# pixelAdapter_l432_pro.net
KiCad netlist of a schematic drawn in EAGLE
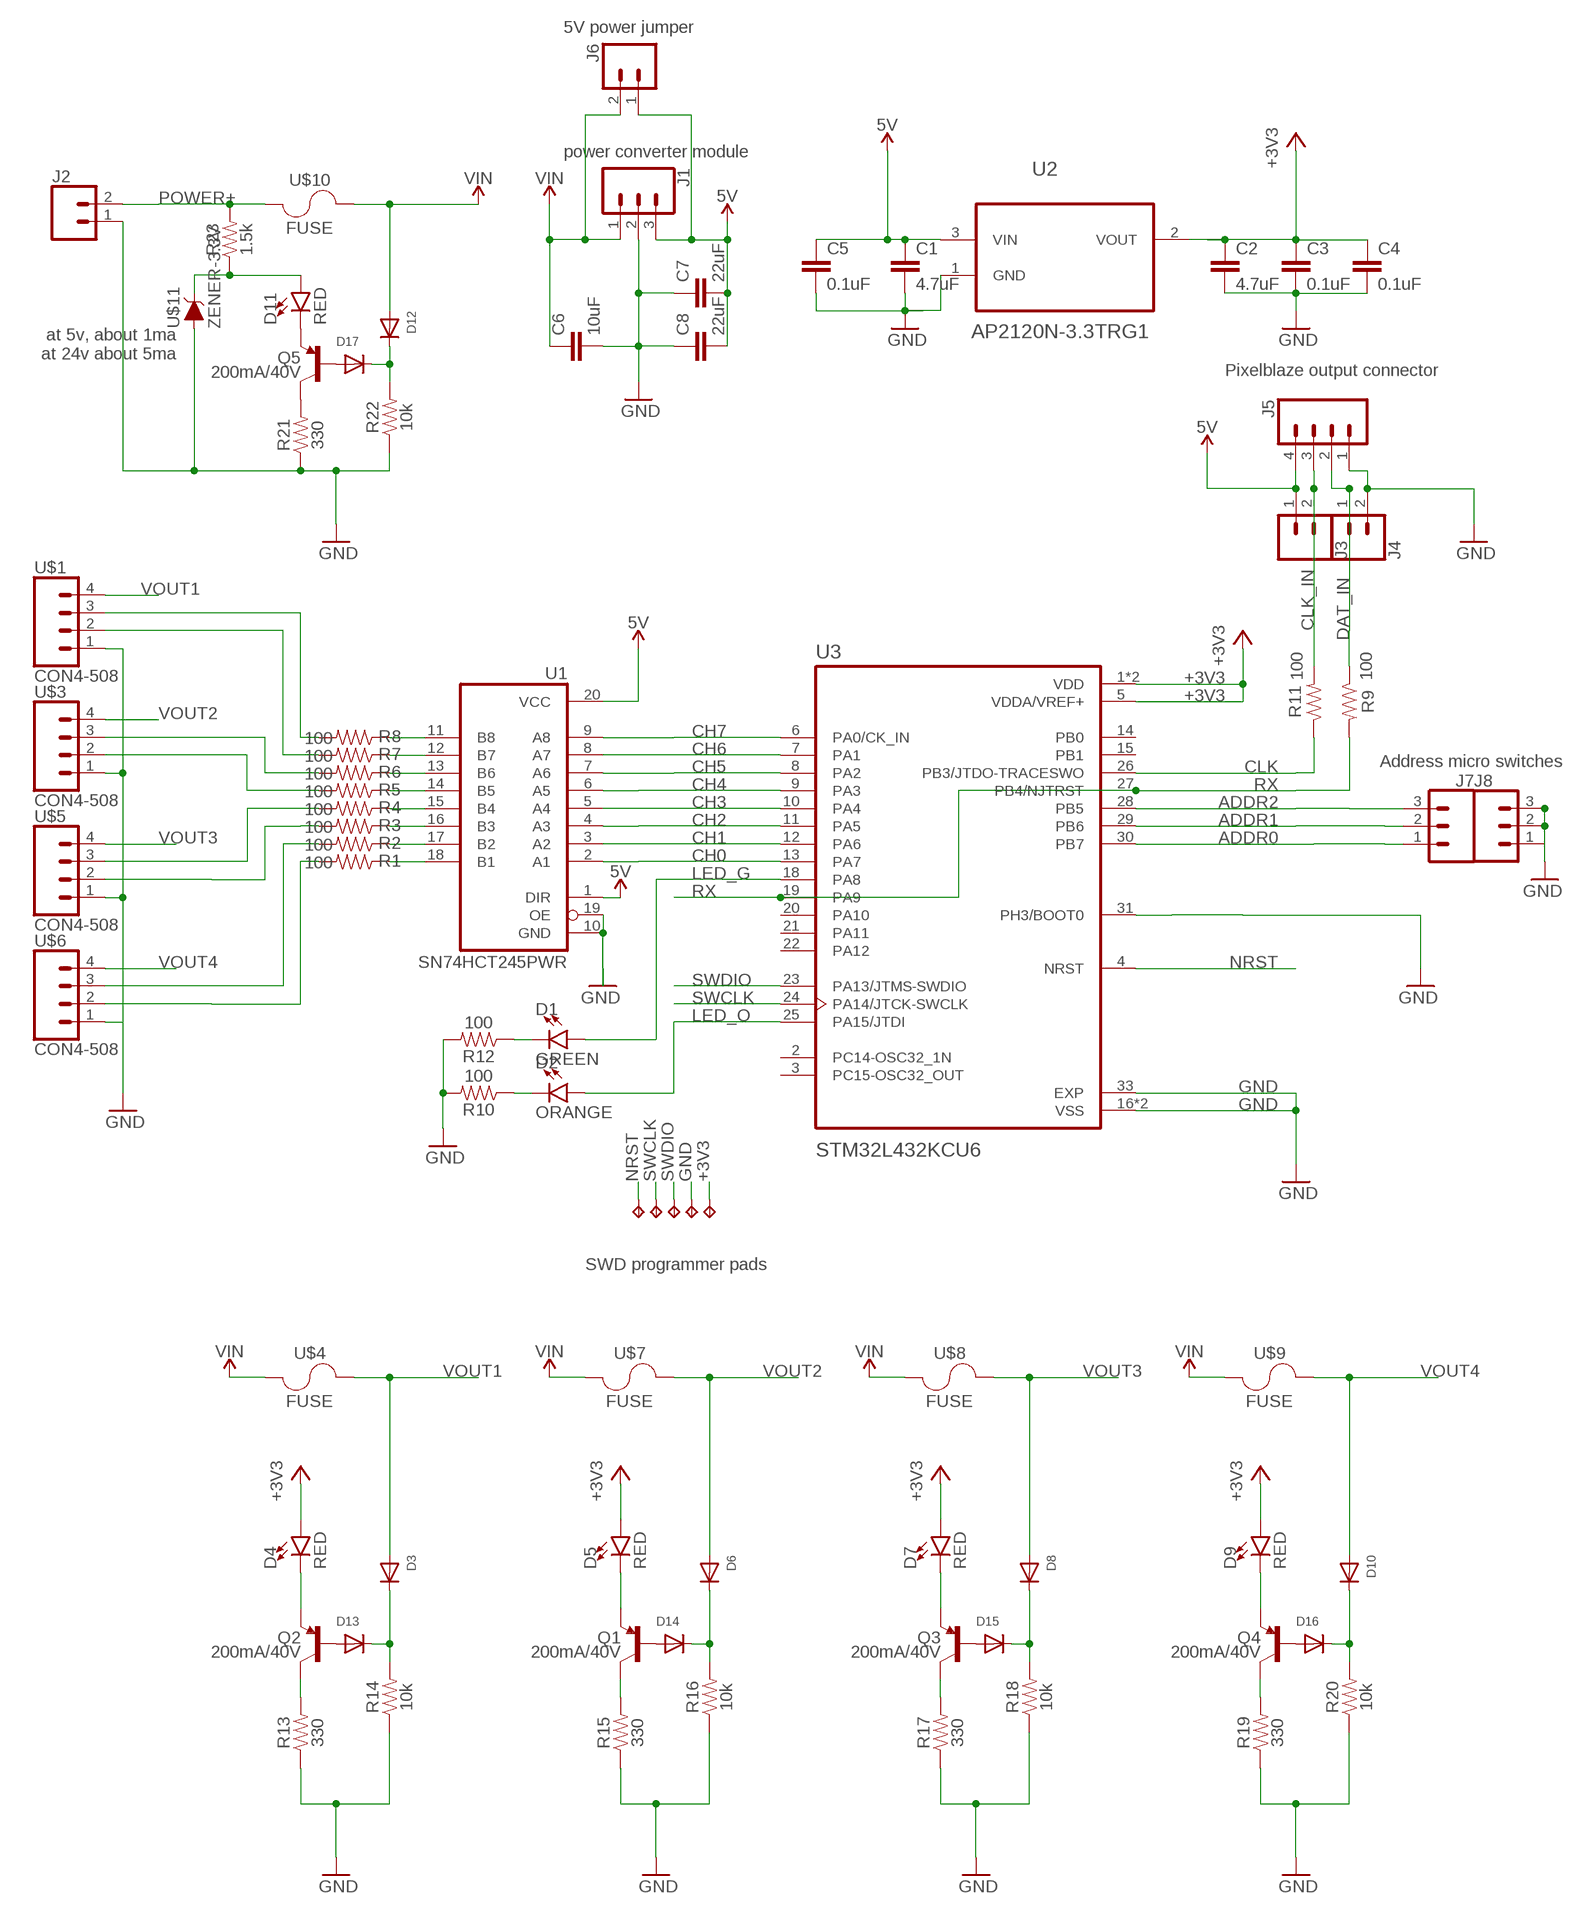
[diagram p0: schematic, sheet 1]

(export (version "E")
  (design (tool "Eeschema 10.0.6"))
  (components
    (comp (ref "C1")
      (value "4.7uF")
      (footprint "eagle-import:0603")
      (libsource (lib "eagle-import") (part "4.7UF0603"))
    )
    (comp (ref "C2")
      (value "4.7uF")
      (footprint "eagle-import:0603")
      (libsource (lib "eagle-import") (part "4.7UF0603"))
    )
    (comp (ref "C3")
      (value "0.1uF")
      (footprint "eagle-import:0603")
      (libsource (lib "eagle-import") (part "0.1UF-0603-25V-(+80/-20%)"))
    )
    (comp (ref "C4")
      (value "0.1uF")
      (footprint "eagle-import:0603")
      (libsource (lib "eagle-import") (part "0.1UF-0603-25V-(+80/-20%)"))
    )
    (comp (ref "C5")
      (value "0.1uF")
      (footprint "eagle-import:0603")
      (libsource (lib "eagle-import") (part "0.1UF-0603-25V-(+80/-20%)"))
    )
    (comp (ref "C6")
      (value "10uF")
      (footprint "eagle-import:1210")
      (libsource (lib "eagle-import") (part "10UF-1210-50V-20%"))
    )
    (comp (ref "C7")
      (value "22uF")
      (footprint "eagle-import:1210")
      (libsource (lib "eagle-import") (part "22UF-1210-16V-20%"))
    )
    (comp (ref "C8")
      (value "22uF")
      (footprint "eagle-import:1210")
      (libsource (lib "eagle-import") (part "22UF-1210-16V-20%"))
    )
    (comp (ref "D1")
      (value "GREEN")
      (footprint "eagle-import:LED-0603")
      (libsource (lib "eagle-import") (part "LED0603"))
    )
    (comp (ref "D2")
      (value "ORANGE")
      (footprint "eagle-import:LED-0603")
      (libsource (lib "eagle-import") (part "LED0603"))
    )
    (comp (ref "D3")
      (value "DIODESOD-123")
      (footprint "eagle-import:SOD-123")
      (libsource (lib "eagle-import") (part "DIODESOD-123"))
    )
    (comp (ref "D4")
      (value "RED")
      (footprint "eagle-import:LED-0603")
      (libsource (lib "eagle-import") (part "LED-RED0603"))
    )
    (comp (ref "D5")
      (value "RED")
      (footprint "eagle-import:LED-0603")
      (libsource (lib "eagle-import") (part "LED-RED0603"))
    )
    (comp (ref "D6")
      (value "DIODESOD-123")
      (footprint "eagle-import:SOD-123")
      (libsource (lib "eagle-import") (part "DIODESOD-123"))
    )
    (comp (ref "D7")
      (value "RED")
      (footprint "eagle-import:LED-0603")
      (libsource (lib "eagle-import") (part "LED-RED0603"))
    )
    (comp (ref "D8")
      (value "DIODESOD-123")
      (footprint "eagle-import:SOD-123")
      (libsource (lib "eagle-import") (part "DIODESOD-123"))
    )
    (comp (ref "D9")
      (value "RED")
      (footprint "eagle-import:LED-0603")
      (libsource (lib "eagle-import") (part "LED-RED0603"))
    )
    (comp (ref "D10")
      (value "DIODESOD-123")
      (footprint "eagle-import:SOD-123")
      (libsource (lib "eagle-import") (part "DIODESOD-123"))
    )
    (comp (ref "D11")
      (value "RED")
      (footprint "eagle-import:LED-0603")
      (libsource (lib "eagle-import") (part "LED-RED0603"))
    )
    (comp (ref "D12")
      (value "DIODESOD-123")
      (footprint "eagle-import:SOD-123")
      (libsource (lib "eagle-import") (part "DIODESOD-123"))
    )
    (comp (ref "D13")
      (value "DIODESOD-123")
      (footprint "eagle-import:SOD-123")
      (libsource (lib "eagle-import") (part "DIODESOD-123"))
    )
    (comp (ref "D14")
      (value "DIODESOD-123")
      (footprint "eagle-import:SOD-123")
      (libsource (lib "eagle-import") (part "DIODESOD-123"))
    )
    (comp (ref "D15")
      (value "DIODESOD-123")
      (footprint "eagle-import:SOD-123")
      (libsource (lib "eagle-import") (part "DIODESOD-123"))
    )
    (comp (ref "D16")
      (value "DIODESOD-123")
      (footprint "eagle-import:SOD-123")
      (libsource (lib "eagle-import") (part "DIODESOD-123"))
    )
    (comp (ref "D17")
      (value "DIODESOD-123")
      (footprint "eagle-import:SOD-123")
      (libsource (lib "eagle-import") (part "DIODESOD-123"))
    )
    (comp (ref "J1")
      (value "CONN_03")
      (footprint "eagle-import:1X03")
      (libsource (lib "eagle-import") (part "CONN_03"))
    )
    (comp (ref "J2")
      (value "CONN_025MM")
      (footprint "eagle-import:SCREWTERMINAL-5MM-2")
      (libsource (lib "eagle-import") (part "bens_CONN_025MM"))
    )
    (comp (ref "J3")
      (value "CONN_025MM")
      (footprint "eagle-import:SCREWTERMINAL-5MM-2")
      (libsource (lib "eagle-import") (part "bens_CONN_025MM"))
    )
    (comp (ref "J4")
      (value "CONN_025MM")
      (footprint "eagle-import:SCREWTERMINAL-5MM-2")
      (libsource (lib "eagle-import") (part "bens_CONN_025MM"))
    )
    (comp (ref "J5")
      (value "CONN_04LOCK")
      (footprint "eagle-import:1X04_LOCK")
      (libsource (lib "eagle-import") (part "CONN_04LOCK"))
    )
    (comp (ref "J6")
      (value "CONN_02")
      (footprint "eagle-import:1X02")
      (libsource (lib "eagle-import") (part "CONN_02"))
    )
    (comp (ref "J7")
      (value "CONN_03LOCK")
      (footprint "eagle-import:1X03_LOCK")
      (libsource (lib "eagle-import") (part "CONN_03LOCK"))
    )
    (comp (ref "J8")
      (value "CONN_03LOCK")
      (footprint "eagle-import:1X03_LOCK")
      (libsource (lib "eagle-import") (part "CONN_03LOCK"))
    )
    (comp (ref "Q1")
      (value "200mA/40V")
      (footprint "eagle-import:SOT23-3")
      (libsource (lib "eagle-import") (part "TRANS_PNP-PMBT3906|MMBT3906L"))
    )
    (comp (ref "Q2")
      (value "200mA/40V")
      (footprint "eagle-import:SOT23-3")
      (libsource (lib "eagle-import") (part "TRANS_PNP-PMBT3906|MMBT3906L"))
    )
    (comp (ref "Q3")
      (value "200mA/40V")
      (footprint "eagle-import:SOT23-3")
      (libsource (lib "eagle-import") (part "TRANS_PNP-PMBT3906|MMBT3906L"))
    )
    (comp (ref "Q4")
      (value "200mA/40V")
      (footprint "eagle-import:SOT23-3")
      (libsource (lib "eagle-import") (part "TRANS_PNP-PMBT3906|MMBT3906L"))
    )
    (comp (ref "Q5")
      (value "200mA/40V")
      (footprint "eagle-import:SOT23-3")
      (libsource (lib "eagle-import") (part "TRANS_PNP-PMBT3906|MMBT3906L"))
    )
    (comp (ref "R1")
      (value "100")
      (footprint "eagle-import:0603")
      (libsource (lib "eagle-import") (part "100OHM-0603-1/10W-1%"))
    )
    (comp (ref "R2")
      (value "100")
      (footprint "eagle-import:0603")
      (libsource (lib "eagle-import") (part "100OHM-0603-1/10W-1%"))
    )
    (comp (ref "R3")
      (value "100")
      (footprint "eagle-import:0603")
      (libsource (lib "eagle-import") (part "100OHM-0603-1/10W-1%"))
    )
    (comp (ref "R4")
      (value "100")
      (footprint "eagle-import:0603")
      (libsource (lib "eagle-import") (part "100OHM-0603-1/10W-1%"))
    )
    (comp (ref "R5")
      (value "100")
      (footprint "eagle-import:0603")
      (libsource (lib "eagle-import") (part "100OHM-0603-1/10W-1%"))
    )
    (comp (ref "R6")
      (value "100")
      (footprint "eagle-import:0603")
      (libsource (lib "eagle-import") (part "100OHM-0603-1/10W-1%"))
    )
    (comp (ref "R7")
      (value "100")
      (footprint "eagle-import:0603")
      (libsource (lib "eagle-import") (part "100OHM-0603-1/10W-1%"))
    )
    (comp (ref "R8")
      (value "100")
      (footprint "eagle-import:0603")
      (libsource (lib "eagle-import") (part "100OHM-0603-1/10W-1%"))
    )
    (comp (ref "R9")
      (value "100")
      (footprint "eagle-import:0603")
      (libsource (lib "eagle-import") (part "100OHM-0603-1/10W-1%"))
    )
    (comp (ref "R10")
      (value "100")
      (footprint "eagle-import:0603")
      (libsource (lib "eagle-import") (part "100OHM-0603-1/10W-1%"))
    )
    (comp (ref "R11")
      (value "100")
      (footprint "eagle-import:0603")
      (libsource (lib "eagle-import") (part "100OHM-0603-1/10W-1%"))
    )
    (comp (ref "R12")
      (value "100")
      (footprint "eagle-import:0603")
      (libsource (lib "eagle-import") (part "100OHM-0603-1/10W-1%"))
    )
    (comp (ref "R13")
      (value "330")
      (footprint "eagle-import:0603")
      (libsource (lib "eagle-import") (part "RESISTOR0603"))
    )
    (comp (ref "R14")
      (value "10k")
      (footprint "eagle-import:0603")
      (libsource (lib "eagle-import") (part "10KOHM-0603-1/10W-1%"))
    )
    (comp (ref "R15")
      (value "330")
      (footprint "eagle-import:0603")
      (libsource (lib "eagle-import") (part "RESISTOR0603"))
    )
    (comp (ref "R16")
      (value "10k")
      (footprint "eagle-import:0603")
      (libsource (lib "eagle-import") (part "10KOHM-0603-1/10W-1%"))
    )
    (comp (ref "R17")
      (value "330")
      (footprint "eagle-import:0603")
      (libsource (lib "eagle-import") (part "RESISTOR0603"))
    )
    (comp (ref "R18")
      (value "10k")
      (footprint "eagle-import:0603")
      (libsource (lib "eagle-import") (part "10KOHM-0603-1/10W-1%"))
    )
    (comp (ref "R19")
      (value "330")
      (footprint "eagle-import:0603")
      (libsource (lib "eagle-import") (part "RESISTOR0603"))
    )
    (comp (ref "R20")
      (value "10k")
      (footprint "eagle-import:0603")
      (libsource (lib "eagle-import") (part "10KOHM-0603-1/10W-1%"))
    )
    (comp (ref "R21")
      (value "330")
      (footprint "eagle-import:0603")
      (libsource (lib "eagle-import") (part "RESISTOR0603"))
    )
    (comp (ref "R22")
      (value "10k")
      (footprint "eagle-import:0603")
      (libsource (lib "eagle-import") (part "10KOHM-0603-1/10W-1%"))
    )
    (comp (ref "R23")
      (value "1.5k")
      (footprint "eagle-import:0603")
      (libsource (lib "eagle-import") (part "1.5KOHM-0603-1/10W-1%"))
    )
    (comp (ref "TP1")
      (value "TPTP20SQ")
      (footprint "eagle-import:TP20SQ")
      (libsource (lib "eagle-import") (part "TPTP20SQ"))
    )
    (comp (ref "TP2")
      (value "TPTP20SQ")
      (footprint "eagle-import:TP20SQ")
      (libsource (lib "eagle-import") (part "TPTP20SQ"))
    )
    (comp (ref "TP3")
      (value "TPTP20SQ")
      (footprint "eagle-import:TP20SQ")
      (libsource (lib "eagle-import") (part "TPTP20SQ"))
    )
    (comp (ref "TP4")
      (value "TPTP20SQ")
      (footprint "eagle-import:TP20SQ")
      (libsource (lib "eagle-import") (part "TPTP20SQ"))
    )
    (comp (ref "TP5")
      (value "TPTP20SQ")
      (footprint "eagle-import:TP20SQ")
      (libsource (lib "eagle-import") (part "TPTP20SQ"))
    )
    (comp (ref "U$1")
      (value "CON4-508")
      (footprint "eagle-import:CON4-508")
      (libsource (lib "eagle-import") (part "CON4-508"))
    )
    (comp (ref "U$3")
      (value "CON4-508")
      (footprint "eagle-import:CON4-508")
      (libsource (lib "eagle-import") (part "CON4-508"))
    )
    (comp (ref "U$4")
      (value "FUSE")
      (footprint "eagle-import:KEYSTONE-3586-FUSEHOLDER")
      (libsource (lib "eagle-import") (part "FUSE"))
    )
    (comp (ref "U$5")
      (value "CON4-508")
      (footprint "eagle-import:CON4-508")
      (libsource (lib "eagle-import") (part "CON4-508"))
    )
    (comp (ref "U$6")
      (value "CON4-508")
      (footprint "eagle-import:CON4-508")
      (libsource (lib "eagle-import") (part "CON4-508"))
    )
    (comp (ref "U$7")
      (value "FUSE")
      (footprint "eagle-import:KEYSTONE-3586-FUSEHOLDER")
      (libsource (lib "eagle-import") (part "FUSE"))
    )
    (comp (ref "U$8")
      (value "FUSE")
      (footprint "eagle-import:KEYSTONE-3586-FUSEHOLDER")
      (libsource (lib "eagle-import") (part "FUSE"))
    )
    (comp (ref "U$9")
      (value "FUSE")
      (footprint "eagle-import:KEYSTONE-3586-FUSEHOLDER")
      (libsource (lib "eagle-import") (part "FUSE"))
    )
    (comp (ref "U$10")
      (value "FUSE")
      (footprint "eagle-import:KEYSTONE-3586-FUSEHOLDER")
      (libsource (lib "eagle-import") (part "FUSE"))
    )
    (comp (ref "U$11")
      (value "ZENER-3.3V")
      (footprint "eagle-import:SOD-123FL")
      (libsource (lib "eagle-import") (part "ZENER"))
    )
    (comp (ref "U1")
      (value "SN74HCT245PWR")
      (footprint "eagle-import:TSSOP20")
      (libsource (lib "eagle-import") (part "74245PW"))
    )
    (comp (ref "U2")
      (value "AP2120N-3.3TRG1")
      (footprint "eagle-import:SOT95P237X112-3N")
      (fields (field (name "MPN") "MCP1700T-3302E/TT"))
      (libsource (lib "eagle-import") (part "MCP1700T-3302E/TT"))
    )
    (comp (ref "U3")
      (value "STM32L432KCU6")
      (footprint "eagle-import:QFN50P500X500X60-33N")
      (fields (field (name "MF") "STMicroelectronics"))
      (libsource (lib "eagle-import") (part "STM32L432KCU6"))
    )
  )
  (nets
    (net (code "1") (name "+3V3") (class "Default")
      (node (ref "C2") (pin "1") (pinfunction "1_1") (pintype "passive"))
      (node (ref "C3") (pin "1") (pinfunction "1_1") (pintype "passive"))
      (node (ref "C4") (pin "1") (pinfunction "1_1") (pintype "passive"))
      (node (ref "D4") (pin "A") (pinfunction "A_A") (pintype "passive"))
      (node (ref "D5") (pin "A") (pinfunction "A_A") (pintype "passive"))
      (node (ref "D7") (pin "A") (pinfunction "A_A") (pintype "passive"))
      (node (ref "D9") (pin "A") (pinfunction "A_A") (pintype "passive"))
      (node (ref "TP4") (pin "TP") (pinfunction "TP_TP") (pintype "input"))
      (node (ref "U2") (pin "2") (pinfunction "VOUT_2") (pintype "output"))
      (node (ref "U3") (pin "1") (pinfunction "VDD_1") (pintype "power_in"))
      (node (ref "U3") (pin "17") (pinfunction "VDD_17") (pintype "power_in"))
      (node (ref "U3") (pin "5") (pinfunction "VDDA/VREF+_5") (pintype "power_in"))
    )
    (net (code "2") (name "/ADDR0") (class "Default")
      (node (ref "J7") (pin "1") (pinfunction "1_1") (pintype "passive"))
      (node (ref "U3") (pin "30") (pinfunction "PB7_30") (pintype "bidirectional"))
    )
    (net (code "3") (name "/ADDR1") (class "Default")
      (node (ref "J7") (pin "2") (pinfunction "2_2") (pintype "passive"))
      (node (ref "U3") (pin "29") (pinfunction "PB6_29") (pintype "bidirectional"))
    )
    (net (code "4") (name "/ADDR2") (class "Default")
      (node (ref "J7") (pin "3") (pinfunction "3_3") (pintype "passive"))
      (node (ref "U3") (pin "28") (pinfunction "PB5_28") (pintype "bidirectional"))
    )
    (net (code "5") (name "/CH0") (class "Default")
      (node (ref "U1") (pin "2") (pinfunction "A1_2") (pintype "bidirectional"))
      (node (ref "U3") (pin "13") (pinfunction "PA7_13") (pintype "bidirectional"))
    )
    (net (code "6") (name "/CH1") (class "Default")
      (node (ref "U1") (pin "3") (pinfunction "A2_3") (pintype "bidirectional"))
      (node (ref "U3") (pin "12") (pinfunction "PA6_12") (pintype "bidirectional"))
    )
    (net (code "7") (name "/CH2") (class "Default")
      (node (ref "U1") (pin "4") (pinfunction "A3_4") (pintype "bidirectional"))
      (node (ref "U3") (pin "11") (pinfunction "PA5_11") (pintype "bidirectional"))
    )
    (net (code "8") (name "/CH3") (class "Default")
      (node (ref "U1") (pin "5") (pinfunction "A4_5") (pintype "bidirectional"))
      (node (ref "U3") (pin "10") (pinfunction "PA4_10") (pintype "bidirectional"))
    )
    (net (code "9") (name "/CH4") (class "Default")
      (node (ref "U1") (pin "6") (pinfunction "A5_6") (pintype "bidirectional"))
      (node (ref "U3") (pin "9") (pinfunction "PA3_9") (pintype "bidirectional"))
    )
    (net (code "10") (name "/CH5") (class "Default")
      (node (ref "U1") (pin "7") (pinfunction "A6_7") (pintype "bidirectional"))
      (node (ref "U3") (pin "8") (pinfunction "PA2_8") (pintype "bidirectional"))
    )
    (net (code "11") (name "/CH6") (class "Default")
      (node (ref "U1") (pin "8") (pinfunction "A7_8") (pintype "bidirectional"))
      (node (ref "U3") (pin "7") (pinfunction "PA1_7") (pintype "bidirectional"))
    )
    (net (code "12") (name "/CH7") (class "Default")
      (node (ref "U1") (pin "9") (pinfunction "A8_9") (pintype "bidirectional"))
      (node (ref "U3") (pin "6") (pinfunction "PA0/CK_IN_6") (pintype "bidirectional"))
    )
    (net (code "13") (name "/CLK") (class "Default")
      (node (ref "R11") (pin "1") (pinfunction "1_1") (pintype "passive"))
      (node (ref "U3") (pin "26") (pinfunction "PB3/JTDO-TRACESWO_26") (pintype "bidirectional"))
    )
    (net (code "14") (name "/CLK_IN") (class "Default")
      (node (ref "J3") (pin "2") (pinfunction "2_2") (pintype "passive"))
      (node (ref "J5") (pin "3") (pinfunction "3_3") (pintype "passive"))
      (node (ref "R11") (pin "2") (pinfunction "2_2") (pintype "passive"))
    )
    (net (code "15") (name "/DAT_IN") (class "Default")
      (node (ref "J4") (pin "1") (pinfunction "1_1") (pintype "passive"))
      (node (ref "J5") (pin "2") (pinfunction "2_2") (pintype "passive"))
      (node (ref "R9") (pin "1") (pinfunction "1_1") (pintype "passive"))
    )
    (net (code "16") (name "/LED_G") (class "Default")
      (node (ref "D1") (pin "A") (pinfunction "A_A") (pintype "passive"))
      (node (ref "U3") (pin "18") (pinfunction "PA8_18") (pintype "bidirectional"))
    )
    (net (code "17") (name "/LED_O") (class "Default")
      (node (ref "D2") (pin "A") (pinfunction "A_A") (pintype "passive"))
      (node (ref "U3") (pin "25") (pinfunction "PA15/JTDI_25") (pintype "bidirectional"))
    )
    (net (code "18") (name "/NRST") (class "Default")
      (node (ref "TP5") (pin "TP") (pinfunction "TP_TP") (pintype "input"))
      (node (ref "U3") (pin "4") (pinfunction "NRST_4") (pintype "bidirectional"))
    )
    (net (code "19") (name "/POWER+") (class "Default")
      (node (ref "J2") (pin "2") (pinfunction "2_2") (pintype "passive"))
      (node (ref "R23") (pin "2") (pinfunction "2_2") (pintype "passive"))
      (node (ref "U$10") (pin "A1") (pinfunction "1_A1") (pintype "bidirectional"))
      (node (ref "U$10") (pin "A2") (pinfunction "1_A2") (pintype "bidirectional"))
      (node (ref "U$10") (pin "A3") (pinfunction "1_A3") (pintype "bidirectional"))
    )
    (net (code "20") (name "/RX") (class "Default")
      (node (ref "R9") (pin "2") (pinfunction "2_2") (pintype "passive"))
      (node (ref "U3") (pin "19") (pinfunction "PA9_19") (pintype "bidirectional"))
      (node (ref "U3") (pin "27") (pinfunction "PB4/NJTRST_27") (pintype "bidirectional"))
    )
    (net (code "21") (name "/SWCLK") (class "Default")
      (node (ref "TP1") (pin "TP") (pinfunction "TP_TP") (pintype "input"))
      (node (ref "U3") (pin "24") (pinfunction "PA14/JTCK-SWCLK_24") (pintype "bidirectional"))
    )
    (net (code "22") (name "/SWDIO") (class "Default")
      (node (ref "TP2") (pin "TP") (pinfunction "TP_TP") (pintype "input"))
      (node (ref "U3") (pin "23") (pinfunction "PA13/JTMS-SWDIO_23") (pintype "bidirectional"))
    )
    (net (code "23") (name "/VOUT1") (class "Default")
      (node (ref "D3") (pin "A") (pinfunction "A_A") (pintype "passive"))
      (node (ref "U$1") (pin "4") (pinfunction "4_4") (pintype "passive"))
      (node (ref "U$4") (pin "B1") (pinfunction "2_B1") (pintype "bidirectional"))
      (node (ref "U$4") (pin "B2") (pinfunction "2_B2") (pintype "bidirectional"))
      (node (ref "U$4") (pin "B3") (pinfunction "2_B3") (pintype "bidirectional"))
    )
    (net (code "24") (name "/VOUT2") (class "Default")
      (node (ref "D6") (pin "A") (pinfunction "A_A") (pintype "passive"))
      (node (ref "U$3") (pin "4") (pinfunction "4_4") (pintype "passive"))
      (node (ref "U$7") (pin "B1") (pinfunction "2_B1") (pintype "bidirectional"))
      (node (ref "U$7") (pin "B2") (pinfunction "2_B2") (pintype "bidirectional"))
      (node (ref "U$7") (pin "B3") (pinfunction "2_B3") (pintype "bidirectional"))
    )
    (net (code "25") (name "/VOUT3") (class "Default")
      (node (ref "D8") (pin "A") (pinfunction "A_A") (pintype "passive"))
      (node (ref "U$5") (pin "4") (pinfunction "4_4") (pintype "passive"))
      (node (ref "U$8") (pin "B1") (pinfunction "2_B1") (pintype "bidirectional"))
      (node (ref "U$8") (pin "B2") (pinfunction "2_B2") (pintype "bidirectional"))
      (node (ref "U$8") (pin "B3") (pinfunction "2_B3") (pintype "bidirectional"))
    )
    (net (code "26") (name "/VOUT4") (class "Default")
      (node (ref "D10") (pin "A") (pinfunction "A_A") (pintype "passive"))
      (node (ref "U$6") (pin "4") (pinfunction "4_4") (pintype "passive"))
      (node (ref "U$9") (pin "B1") (pinfunction "2_B1") (pintype "bidirectional"))
      (node (ref "U$9") (pin "B2") (pinfunction "2_B2") (pintype "bidirectional"))
      (node (ref "U$9") (pin "B3") (pinfunction "2_B3") (pintype "bidirectional"))
    )
    (net (code "27") (name "5V") (class "Default")
      (node (ref "C1") (pin "1") (pinfunction "1_1") (pintype "passive"))
      (node (ref "C5") (pin "1") (pinfunction "1_1") (pintype "passive"))
      (node (ref "C7") (pin "2") (pinfunction "2_2") (pintype "passive"))
      (node (ref "C8") (pin "2") (pinfunction "2_2") (pintype "passive"))
      (node (ref "J1") (pin "3") (pinfunction "3_3") (pintype "passive"))
      (node (ref "J3") (pin "1") (pinfunction "1_1") (pintype "passive"))
      (node (ref "J5") (pin "4") (pinfunction "4_4") (pintype "passive"))
      (node (ref "J6") (pin "1") (pinfunction "1_1") (pintype "passive"))
      (node (ref "U1") (pin "1") (pinfunction "DIR_1") (pintype "input"))
      (node (ref "U1") (pin "20") (pinfunction "VCC_20") (pintype "bidirectional"))
      (node (ref "U2") (pin "3") (pinfunction "VIN_3") (pintype "input"))
    )
    (net (code "28") (name "GND") (class "Default")
      (node (ref "C1") (pin "2") (pinfunction "2_2") (pintype "passive"))
      (node (ref "C2") (pin "2") (pinfunction "2_2") (pintype "passive"))
      (node (ref "C3") (pin "2") (pinfunction "2_2") (pintype "passive"))
      (node (ref "C4") (pin "2") (pinfunction "2_2") (pintype "passive"))
      (node (ref "C5") (pin "2") (pinfunction "2_2") (pintype "passive"))
      (node (ref "C6") (pin "2") (pinfunction "2_2") (pintype "passive"))
      (node (ref "C7") (pin "1") (pinfunction "1_1") (pintype "passive"))
      (node (ref "C8") (pin "1") (pinfunction "1_1") (pintype "passive"))
      (node (ref "J1") (pin "2") (pinfunction "2_2") (pintype "passive"))
      (node (ref "J2") (pin "1") (pinfunction "1_1") (pintype "passive"))
      (node (ref "J4") (pin "2") (pinfunction "2_2") (pintype "passive"))
      (node (ref "J5") (pin "1") (pinfunction "1_1") (pintype "passive"))
      (node (ref "J8") (pin "1") (pinfunction "1_1") (pintype "passive"))
      (node (ref "J8") (pin "2") (pinfunction "2_2") (pintype "passive"))
      (node (ref "J8") (pin "3") (pinfunction "3_3") (pintype "passive"))
      (node (ref "R10") (pin "2") (pinfunction "2_2") (pintype "passive"))
      (node (ref "R12") (pin "2") (pinfunction "2_2") (pintype "passive"))
      (node (ref "R13") (pin "1") (pinfunction "1_1") (pintype "passive"))
      (node (ref "R14") (pin "1") (pinfunction "1_1") (pintype "passive"))
      (node (ref "R15") (pin "1") (pinfunction "1_1") (pintype "passive"))
      (node (ref "R16") (pin "1") (pinfunction "1_1") (pintype "passive"))
      (node (ref "R17") (pin "1") (pinfunction "1_1") (pintype "passive"))
      (node (ref "R18") (pin "1") (pinfunction "1_1") (pintype "passive"))
      (node (ref "R19") (pin "1") (pinfunction "1_1") (pintype "passive"))
      (node (ref "R20") (pin "1") (pinfunction "1_1") (pintype "passive"))
      (node (ref "R21") (pin "1") (pinfunction "1_1") (pintype "passive"))
      (node (ref "R22") (pin "1") (pinfunction "1_1") (pintype "passive"))
      (node (ref "TP3") (pin "TP") (pinfunction "TP_TP") (pintype "input"))
      (node (ref "U$1") (pin "1") (pinfunction "1_1") (pintype "passive"))
      (node (ref "U$11") (pin "A") (pinfunction "A_A") (pintype "passive"))
      (node (ref "U$3") (pin "1") (pinfunction "1_1") (pintype "passive"))
      (node (ref "U$5") (pin "1") (pinfunction "1_1") (pintype "passive"))
      (node (ref "U$6") (pin "1") (pinfunction "1_1") (pintype "passive"))
      (node (ref "U1") (pin "10") (pinfunction "GND_10") (pintype "bidirectional"))
      (node (ref "U1") (pin "19") (pinfunction "OE_19") (pintype "input"))
      (node (ref "U2") (pin "1") (pinfunction "GND_1") (pintype "passive"))
      (node (ref "U3") (pin "16") (pinfunction "VSS_16") (pintype "power_in"))
      (node (ref "U3") (pin "31") (pinfunction "PH3/BOOT0_31") (pintype "bidirectional"))
      (node (ref "U3") (pin "32") (pinfunction "VSS_32") (pintype "power_in"))
      (node (ref "U3") (pin "33") (pinfunction "EXP_33") (pintype "power_in"))
    )
    (net (code "29") (name "Net-(D1-PadC)") (class "Default")
      (node (ref "D1") (pin "C") (pinfunction "C_C") (pintype "passive"))
      (node (ref "R12") (pin "1") (pinfunction "1_1") (pintype "passive"))
    )
    (net (code "30") (name "Net-(D2-PadC)") (class "Default")
      (node (ref "D2") (pin "C") (pinfunction "C_C") (pintype "passive"))
      (node (ref "R10") (pin "1") (pinfunction "1_1") (pintype "passive"))
    )
    (net (code "31") (name "Net-(D10-PadC)") (class "Default")
      (node (ref "D10") (pin "C") (pinfunction "C_C") (pintype "passive"))
      (node (ref "D16") (pin "C") (pinfunction "C_C") (pintype "passive"))
      (node (ref "R20") (pin "2") (pinfunction "2_2") (pintype "passive"))
    )
    (net (code "32") (name "Net-(D11-PadA)") (class "Default")
      (node (ref "D11") (pin "A") (pinfunction "A_A") (pintype "passive"))
      (node (ref "R23") (pin "1") (pinfunction "1_1") (pintype "passive"))
      (node (ref "U$11") (pin "C") (pinfunction "C_C") (pintype "passive"))
    )
    (net (code "33") (name "Net-(D12-PadC)") (class "Default")
      (node (ref "D12") (pin "C") (pinfunction "C_C") (pintype "passive"))
      (node (ref "D17") (pin "C") (pinfunction "C_C") (pintype "passive"))
      (node (ref "R22") (pin "2") (pinfunction "2_2") (pintype "passive"))
    )
    (net (code "34") (name "Net-(D13-PadC)") (class "Default")
      (node (ref "D13") (pin "C") (pinfunction "C_C") (pintype "passive"))
      (node (ref "D3") (pin "C") (pinfunction "C_C") (pintype "passive"))
      (node (ref "R14") (pin "2") (pinfunction "2_2") (pintype "passive"))
    )
    (net (code "35") (name "Net-(D14-PadC)") (class "Default")
      (node (ref "D14") (pin "C") (pinfunction "C_C") (pintype "passive"))
      (node (ref "D6") (pin "C") (pinfunction "C_C") (pintype "passive"))
      (node (ref "R16") (pin "2") (pinfunction "2_2") (pintype "passive"))
    )
    (net (code "36") (name "Net-(D15-PadC)") (class "Default")
      (node (ref "D15") (pin "C") (pinfunction "C_C") (pintype "passive"))
      (node (ref "D8") (pin "C") (pinfunction "C_C") (pintype "passive"))
      (node (ref "R18") (pin "2") (pinfunction "2_2") (pintype "passive"))
    )
    (net (code "37") (name "Net-(Q1-B)") (class "Default")
      (node (ref "D14") (pin "A") (pinfunction "A_A") (pintype "passive"))
      (node (ref "Q1") (pin "1") (pinfunction "B_1") (pintype "passive"))
    )
    (net (code "38") (name "Net-(Q1-C)") (class "Default")
      (node (ref "Q1") (pin "3") (pinfunction "C_3") (pintype "passive"))
      (node (ref "R15") (pin "2") (pinfunction "2_2") (pintype "passive"))
    )
    (net (code "39") (name "Net-(Q1-E)") (class "Default")
      (node (ref "D5") (pin "C") (pinfunction "C_C") (pintype "passive"))
      (node (ref "Q1") (pin "2") (pinfunction "E_2") (pintype "passive"))
    )
    (net (code "40") (name "Net-(Q2-B)") (class "Default")
      (node (ref "D13") (pin "A") (pinfunction "A_A") (pintype "passive"))
      (node (ref "Q2") (pin "1") (pinfunction "B_1") (pintype "passive"))
    )
    (net (code "41") (name "Net-(Q2-C)") (class "Default")
      (node (ref "Q2") (pin "3") (pinfunction "C_3") (pintype "passive"))
      (node (ref "R13") (pin "2") (pinfunction "2_2") (pintype "passive"))
    )
    (net (code "42") (name "Net-(Q2-E)") (class "Default")
      (node (ref "D4") (pin "C") (pinfunction "C_C") (pintype "passive"))
      (node (ref "Q2") (pin "2") (pinfunction "E_2") (pintype "passive"))
    )
    (net (code "43") (name "Net-(Q3-B)") (class "Default")
      (node (ref "D15") (pin "A") (pinfunction "A_A") (pintype "passive"))
      (node (ref "Q3") (pin "1") (pinfunction "B_1") (pintype "passive"))
    )
    (net (code "44") (name "Net-(Q3-C)") (class "Default")
      (node (ref "Q3") (pin "3") (pinfunction "C_3") (pintype "passive"))
      (node (ref "R17") (pin "2") (pinfunction "2_2") (pintype "passive"))
    )
    (net (code "45") (name "Net-(Q3-E)") (class "Default")
      (node (ref "D7") (pin "C") (pinfunction "C_C") (pintype "passive"))
      (node (ref "Q3") (pin "2") (pinfunction "E_2") (pintype "passive"))
    )
    (net (code "46") (name "Net-(Q4-B)") (class "Default")
      (node (ref "D16") (pin "A") (pinfunction "A_A") (pintype "passive"))
      (node (ref "Q4") (pin "1") (pinfunction "B_1") (pintype "passive"))
    )
    (net (code "47") (name "Net-(Q4-C)") (class "Default")
      (node (ref "Q4") (pin "3") (pinfunction "C_3") (pintype "passive"))
      (node (ref "R19") (pin "2") (pinfunction "2_2") (pintype "passive"))
    )
    (net (code "48") (name "Net-(Q4-E)") (class "Default")
      (node (ref "D9") (pin "C") (pinfunction "C_C") (pintype "passive"))
      (node (ref "Q4") (pin "2") (pinfunction "E_2") (pintype "passive"))
    )
    (net (code "49") (name "Net-(Q5-B)") (class "Default")
      (node (ref "D17") (pin "A") (pinfunction "A_A") (pintype "passive"))
      (node (ref "Q5") (pin "1") (pinfunction "B_1") (pintype "passive"))
    )
    (net (code "50") (name "Net-(Q5-C)") (class "Default")
      (node (ref "Q5") (pin "3") (pinfunction "C_3") (pintype "passive"))
      (node (ref "R21") (pin "2") (pinfunction "2_2") (pintype "passive"))
    )
    (net (code "51") (name "Net-(Q5-E)") (class "Default")
      (node (ref "D11") (pin "C") (pinfunction "C_C") (pintype "passive"))
      (node (ref "Q5") (pin "2") (pinfunction "E_2") (pintype "passive"))
    )
    (net (code "52") (name "Net-(R1-Pad2)") (class "Default")
      (node (ref "R1") (pin "2") (pinfunction "2_2") (pintype "passive"))
      (node (ref "U$6") (pin "2") (pinfunction "2_2") (pintype "passive"))
    )
    (net (code "53") (name "Net-(R2-Pad2)") (class "Default")
      (node (ref "R2") (pin "2") (pinfunction "2_2") (pintype "passive"))
      (node (ref "U$6") (pin "3") (pinfunction "3_3") (pintype "passive"))
    )
    (net (code "54") (name "Net-(R3-Pad2)") (class "Default")
      (node (ref "R3") (pin "2") (pinfunction "2_2") (pintype "passive"))
      (node (ref "U$5") (pin "2") (pinfunction "2_2") (pintype "passive"))
    )
    (net (code "55") (name "Net-(R4-Pad2)") (class "Default")
      (node (ref "R4") (pin "2") (pinfunction "2_2") (pintype "passive"))
      (node (ref "U$5") (pin "3") (pinfunction "3_3") (pintype "passive"))
    )
    (net (code "56") (name "Net-(R5-Pad2)") (class "Default")
      (node (ref "R5") (pin "2") (pinfunction "2_2") (pintype "passive"))
      (node (ref "U$3") (pin "2") (pinfunction "2_2") (pintype "passive"))
    )
    (net (code "57") (name "Net-(R6-Pad2)") (class "Default")
      (node (ref "R6") (pin "2") (pinfunction "2_2") (pintype "passive"))
      (node (ref "U$3") (pin "3") (pinfunction "3_3") (pintype "passive"))
    )
    (net (code "58") (name "Net-(R7-Pad2)") (class "Default")
      (node (ref "R7") (pin "2") (pinfunction "2_2") (pintype "passive"))
      (node (ref "U$1") (pin "2") (pinfunction "2_2") (pintype "passive"))
    )
    (net (code "59") (name "Net-(R8-Pad2)") (class "Default")
      (node (ref "R8") (pin "2") (pinfunction "2_2") (pintype "passive"))
      (node (ref "U$1") (pin "3") (pinfunction "3_3") (pintype "passive"))
    )
    (net (code "60") (name "Net-(U1-B1)") (class "Default")
      (node (ref "R1") (pin "1") (pinfunction "1_1") (pintype "passive"))
      (node (ref "U1") (pin "18") (pinfunction "B1_18") (pintype "bidirectional"))
    )
    (net (code "61") (name "Net-(U1-B2)") (class "Default")
      (node (ref "R2") (pin "1") (pinfunction "1_1") (pintype "passive"))
      (node (ref "U1") (pin "17") (pinfunction "B2_17") (pintype "bidirectional"))
    )
    (net (code "62") (name "Net-(U1-B3)") (class "Default")
      (node (ref "R3") (pin "1") (pinfunction "1_1") (pintype "passive"))
      (node (ref "U1") (pin "16") (pinfunction "B3_16") (pintype "bidirectional"))
    )
    (net (code "63") (name "Net-(U1-B4)") (class "Default")
      (node (ref "R4") (pin "1") (pinfunction "1_1") (pintype "passive"))
      (node (ref "U1") (pin "15") (pinfunction "B4_15") (pintype "bidirectional"))
    )
    (net (code "64") (name "Net-(U1-B5)") (class "Default")
      (node (ref "R5") (pin "1") (pinfunction "1_1") (pintype "passive"))
      (node (ref "U1") (pin "14") (pinfunction "B5_14") (pintype "bidirectional"))
    )
    (net (code "65") (name "Net-(U1-B6)") (class "Default")
      (node (ref "R6") (pin "1") (pinfunction "1_1") (pintype "passive"))
      (node (ref "U1") (pin "13") (pinfunction "B6_13") (pintype "bidirectional"))
    )
    (net (code "66") (name "Net-(U1-B7)") (class "Default")
      (node (ref "R7") (pin "1") (pinfunction "1_1") (pintype "passive"))
      (node (ref "U1") (pin "12") (pinfunction "B7_12") (pintype "bidirectional"))
    )
    (net (code "67") (name "Net-(U1-B8)") (class "Default")
      (node (ref "R8") (pin "1") (pinfunction "1_1") (pintype "passive"))
      (node (ref "U1") (pin "11") (pinfunction "B8_11") (pintype "bidirectional"))
    )
    (net (code "68") (name "VIN") (class "Default")
      (node (ref "C6") (pin "1") (pinfunction "1_1") (pintype "passive"))
      (node (ref "D12") (pin "A") (pinfunction "A_A") (pintype "passive"))
      (node (ref "J1") (pin "1") (pinfunction "1_1") (pintype "passive"))
      (node (ref "J6") (pin "2") (pinfunction "2_2") (pintype "passive"))
      (node (ref "U$10") (pin "B1") (pinfunction "2_B1") (pintype "bidirectional"))
      (node (ref "U$10") (pin "B2") (pinfunction "2_B2") (pintype "bidirectional"))
      (node (ref "U$10") (pin "B3") (pinfunction "2_B3") (pintype "bidirectional"))
      (node (ref "U$4") (pin "A1") (pinfunction "1_A1") (pintype "bidirectional"))
      (node (ref "U$4") (pin "A2") (pinfunction "1_A2") (pintype "bidirectional"))
      (node (ref "U$4") (pin "A3") (pinfunction "1_A3") (pintype "bidirectional"))
      (node (ref "U$7") (pin "A1") (pinfunction "1_A1") (pintype "bidirectional"))
      (node (ref "U$7") (pin "A2") (pinfunction "1_A2") (pintype "bidirectional"))
      (node (ref "U$7") (pin "A3") (pinfunction "1_A3") (pintype "bidirectional"))
      (node (ref "U$8") (pin "A1") (pinfunction "1_A1") (pintype "bidirectional"))
      (node (ref "U$8") (pin "A2") (pinfunction "1_A2") (pintype "bidirectional"))
      (node (ref "U$8") (pin "A3") (pinfunction "1_A3") (pintype "bidirectional"))
      (node (ref "U$9") (pin "A1") (pinfunction "1_A1") (pintype "bidirectional"))
      (node (ref "U$9") (pin "A2") (pinfunction "1_A2") (pintype "bidirectional"))
      (node (ref "U$9") (pin "A3") (pinfunction "1_A3") (pintype "bidirectional"))
    )
    (net (code "69") (name "unconnected-(U3-PA10-Pad20)") (class "Default")
      (node (ref "U3") (pin "20") (pinfunction "PA10_20") (pintype "bidirectional"))
    )
    (net (code "70") (name "unconnected-(U3-PA11-Pad21)") (class "Default")
      (node (ref "U3") (pin "21") (pinfunction "PA11_21") (pintype "bidirectional"))
    )
    (net (code "71") (name "unconnected-(U3-PA12-Pad22)") (class "Default")
      (node (ref "U3") (pin "22") (pinfunction "PA12_22") (pintype "bidirectional"))
    )
    (net (code "72") (name "unconnected-(U3-PB0-Pad14)") (class "Default")
      (node (ref "U3") (pin "14") (pinfunction "PB0_14") (pintype "bidirectional"))
    )
    (net (code "73") (name "unconnected-(U3-PB1-Pad15)") (class "Default")
      (node (ref "U3") (pin "15") (pinfunction "PB1_15") (pintype "bidirectional"))
    )
    (net (code "74") (name "unconnected-(U3-PC14-OSC32_1N-Pad2)") (class "Default")
      (node (ref "U3") (pin "2") (pinfunction "PC14-OSC32_1N_2") (pintype "bidirectional"))
    )
    (net (code "75") (name "unconnected-(U3-PC15-OSC32_OUT-Pad3)") (class "Default")
      (node (ref "U3") (pin "3") (pinfunction "PC15-OSC32_OUT_3") (pintype "bidirectional"))
    )
  )
)
